# untitled.net
KiCad netlist of a schematic drawn in EAGLE
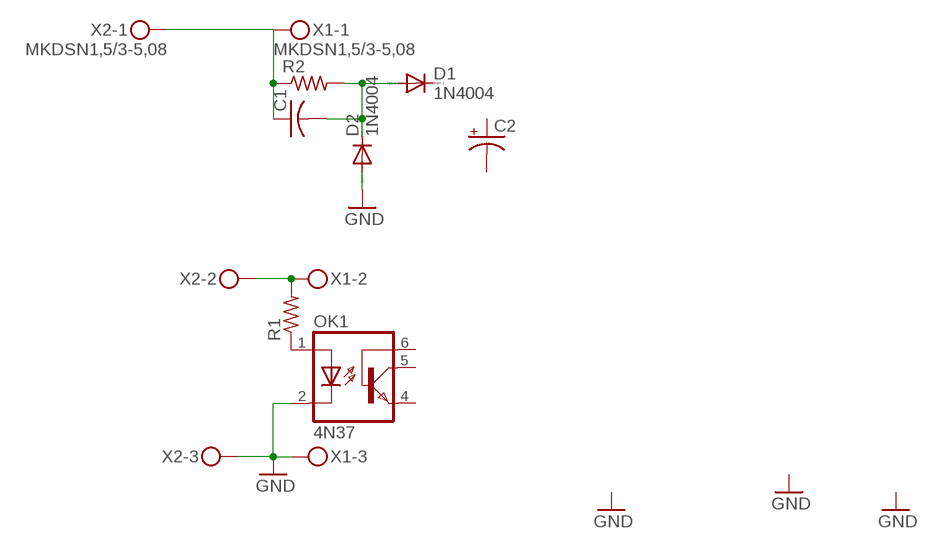
[diagram p0: schematic, sheet 1]

(export (version "E")
  (design (tool "Eeschema 10.0.6"))
  (components
    (comp (ref "C1")
      (value "C-US275-205X316")
      (footprint "eagle-import:C275-205X316")
      (libsource (lib "eagle-import") (part "C-US275-205X316"))
    )
    (comp (ref "C2")
      (value "CPOL-USE5-13")
      (footprint "eagle-import:E5-13")
      (libsource (lib "eagle-import") (part "CPOL-USE5-13"))
    )
    (comp (ref "D1")
      (value "1N4004")
      (footprint "eagle-import:DO41-10")
      (libsource (lib "eagle-import") (part "1N4004"))
    )
    (comp (ref "D2")
      (value "1N4004")
      (footprint "eagle-import:DO41-10")
      (libsource (lib "eagle-import") (part "1N4004"))
    )
    (comp (ref "OK1")
      (value "4N37")
      (footprint "eagle-import:DIL06")
      (fields (field (name "MF") "FAIRCHILD SEMICONDUCTOR"))
      (libsource (lib "eagle-import") (part "4N37"))
    )
    (comp (ref "R1")
      (value "R-US_0617/5V")
      (footprint "eagle-import:0617V")
      (libsource (lib "eagle-import") (part "R-US_0617/5V"))
    )
    (comp (ref "R2")
      (value "R-US_0617/5V")
      (footprint "eagle-import:0617V")
      (libsource (lib "eagle-import") (part "R-US_0617/5V"))
    )
    (comp (ref "X1")
      (value "MKDSN1,5/3-5,08")
      (footprint "eagle-import:MKDSN1,5_3-5,08")
      (libsource (lib "eagle-import") (part "MKDSN1,5/3-5,08"))
    )
    (comp (ref "X2")
      (value "MKDSN1,5/3-5,08")
      (footprint "eagle-import:MKDSN1,5_3-5,08")
      (libsource (lib "eagle-import") (part "MKDSN1,5/3-5,08"))
    )
  )
  (nets
    (net (code "1") (name "GND") (class "Default")
      (node (ref "D2") (pin "A") (pinfunction "A_A") (pintype "passive"))
      (node (ref "OK1") (pin "2") (pinfunction "C_2") (pintype "passive"))
      (node (ref "X1") (pin "3") (pinfunction "KL_3") (pintype "passive"))
      (node (ref "X2") (pin "3") (pinfunction "KL_3") (pintype "passive"))
    )
    (net (code "2") (name "Net-(C1-Pad2)") (class "Default")
      (node (ref "C1") (pin "2") (pinfunction "2_2") (pintype "passive"))
      (node (ref "D1") (pin "A") (pinfunction "A_A") (pintype "passive"))
      (node (ref "D2") (pin "C") (pinfunction "C_C") (pintype "passive"))
      (node (ref "R2") (pin "2") (pinfunction "2_2") (pintype "passive"))
    )
    (net (code "3") (name "Net-(OK1-A)") (class "Default")
      (node (ref "OK1") (pin "1") (pinfunction "A_1") (pintype "passive"))
      (node (ref "R1") (pin "1") (pinfunction "1_1") (pintype "passive"))
    )
    (net (code "4") (name "Net-(X1A-KL)") (class "Default")
      (node (ref "C1") (pin "1") (pinfunction "1_1") (pintype "passive"))
      (node (ref "R2") (pin "1") (pinfunction "1_1") (pintype "passive"))
      (node (ref "X1") (pin "1") (pinfunction "KL_1") (pintype "passive"))
      (node (ref "X2") (pin "1") (pinfunction "KL_1") (pintype "passive"))
    )
    (net (code "5") (name "Net-(X1B-KL)") (class "Default")
      (node (ref "R1") (pin "2") (pinfunction "2_2") (pintype "passive"))
      (node (ref "X1") (pin "2") (pinfunction "KL_2") (pintype "passive"))
      (node (ref "X2") (pin "2") (pinfunction "KL_2") (pintype "passive"))
    )
    (net (code "6") (name "unconnected-(C2-Pad+)") (class "Default")
      (node (ref "C2") (pin "+") (pinfunction "+_+") (pintype "passive"))
    )
    (net (code "7") (name "unconnected-(C2-Pad-)") (class "Default")
      (node (ref "C2") (pin "-") (pinfunction "-_-") (pintype "passive"))
    )
    (net (code "8") (name "unconnected-(D1-PadC)") (class "Default")
      (node (ref "D1") (pin "C") (pinfunction "C_C") (pintype "passive"))
    )
    (net (code "9") (name "unconnected-(OK1-BAS-Pad6)") (class "Default")
      (node (ref "OK1") (pin "6") (pinfunction "BAS_6") (pintype "passive"))
    )
    (net (code "10") (name "unconnected-(OK1-COL-Pad5)") (class "Default")
      (node (ref "OK1") (pin "5") (pinfunction "COL_5") (pintype "passive"))
    )
    (net (code "11") (name "unconnected-(OK1-EMI-Pad4)") (class "Default")
      (node (ref "OK1") (pin "4") (pinfunction "EMI_4") (pintype "passive"))
    )
  )
)
